# 12-TEMPERATURE.net
KiCad netlist of a schematic drawn in Altium Designer
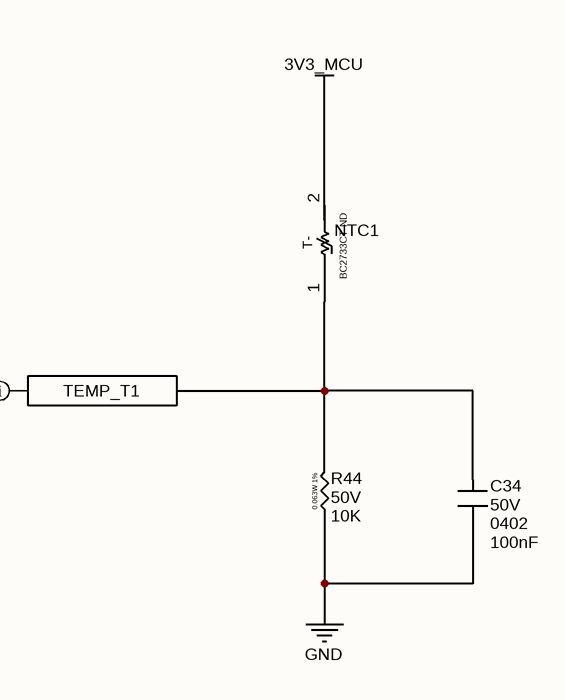
[diagram p0: 12-TEMPERATURE.SchDoc]

(export (version "E")
  (design (tool "Eeschema 10.0.6"))
  (components
    (comp (ref "C34")
      (value "100nF")
      (footprint "C 0402(1005)x0.5")
      (description "SMD-0402 100nF 50V X7R 10%")
      (fields
        (field (name "PART NUMBER") "CL05B104KB5NNNC")
        (field (name "MANUFACTURER") "Samsung")
        (field (name "VDC") "50V")
        (field (name "PACKAGE") "0402")
        (field (name "PUBLISHER") "Hefest")
      )
      (libsource (lib "LIB_PASSIVE") (part "CAP 0402 100nF 50V X7R"))
    )
    (comp (ref "NTC1")
      (value "NTCS0805E3103FLT")
      (footprint "R 0805(2012)")
      (description "THERMISTOR NTC 10KOHM 3430K 0805")
      (fields (field (name "SUPPLIER PART NUMBER 1") "BC2733CT-ND"))
      (libsource (lib "LIB_PASSIVE") (part "NTCS0805E3103FLT"))
    )
    (comp (ref "R44")
      (value "10K")
      (footprint "R 0402(1005)-1%")
      (description "SMD 0402 0.063W 1% 50V")
      (fields
        (field (name "MANUFACTURER") "YAGEO")
        (field (name "POWER") "0.0625W")
        (field (name "VDC") "50V")
        (field (name "PUBLISHER") "Hefest")
      )
      (libsource (lib "LIB_PASSIVE") (part "RES 0402-1%"))
    )
  )
  (nets
    (net (code "1") (name "/TEMP_T1") (class "Default")
      (node (ref "C34") (pin "1") (pinfunction "1_1") (pintype "passive"))
      (node (ref "NTC1") (pin "1") (pinfunction "1_1") (pintype "passive"))
      (node (ref "R44") (pin "2") (pinfunction "2_2") (pintype "passive"))
    )
    (net (code "2") (name "3V3_MCU") (class "Default")
      (node (ref "NTC1") (pin "2") (pinfunction "2_2") (pintype "passive"))
    )
    (net (code "3") (name "GND") (class "Default")
      (node (ref "C34") (pin "2") (pinfunction "2_2") (pintype "passive"))
      (node (ref "R44") (pin "1") (pinfunction "1_1") (pintype "passive"))
    )
  )
)
